# LoraWAN_Soil_Moisture_Sensor_v2_0.net
KiCad netlist of a schematic drawn in EAGLE
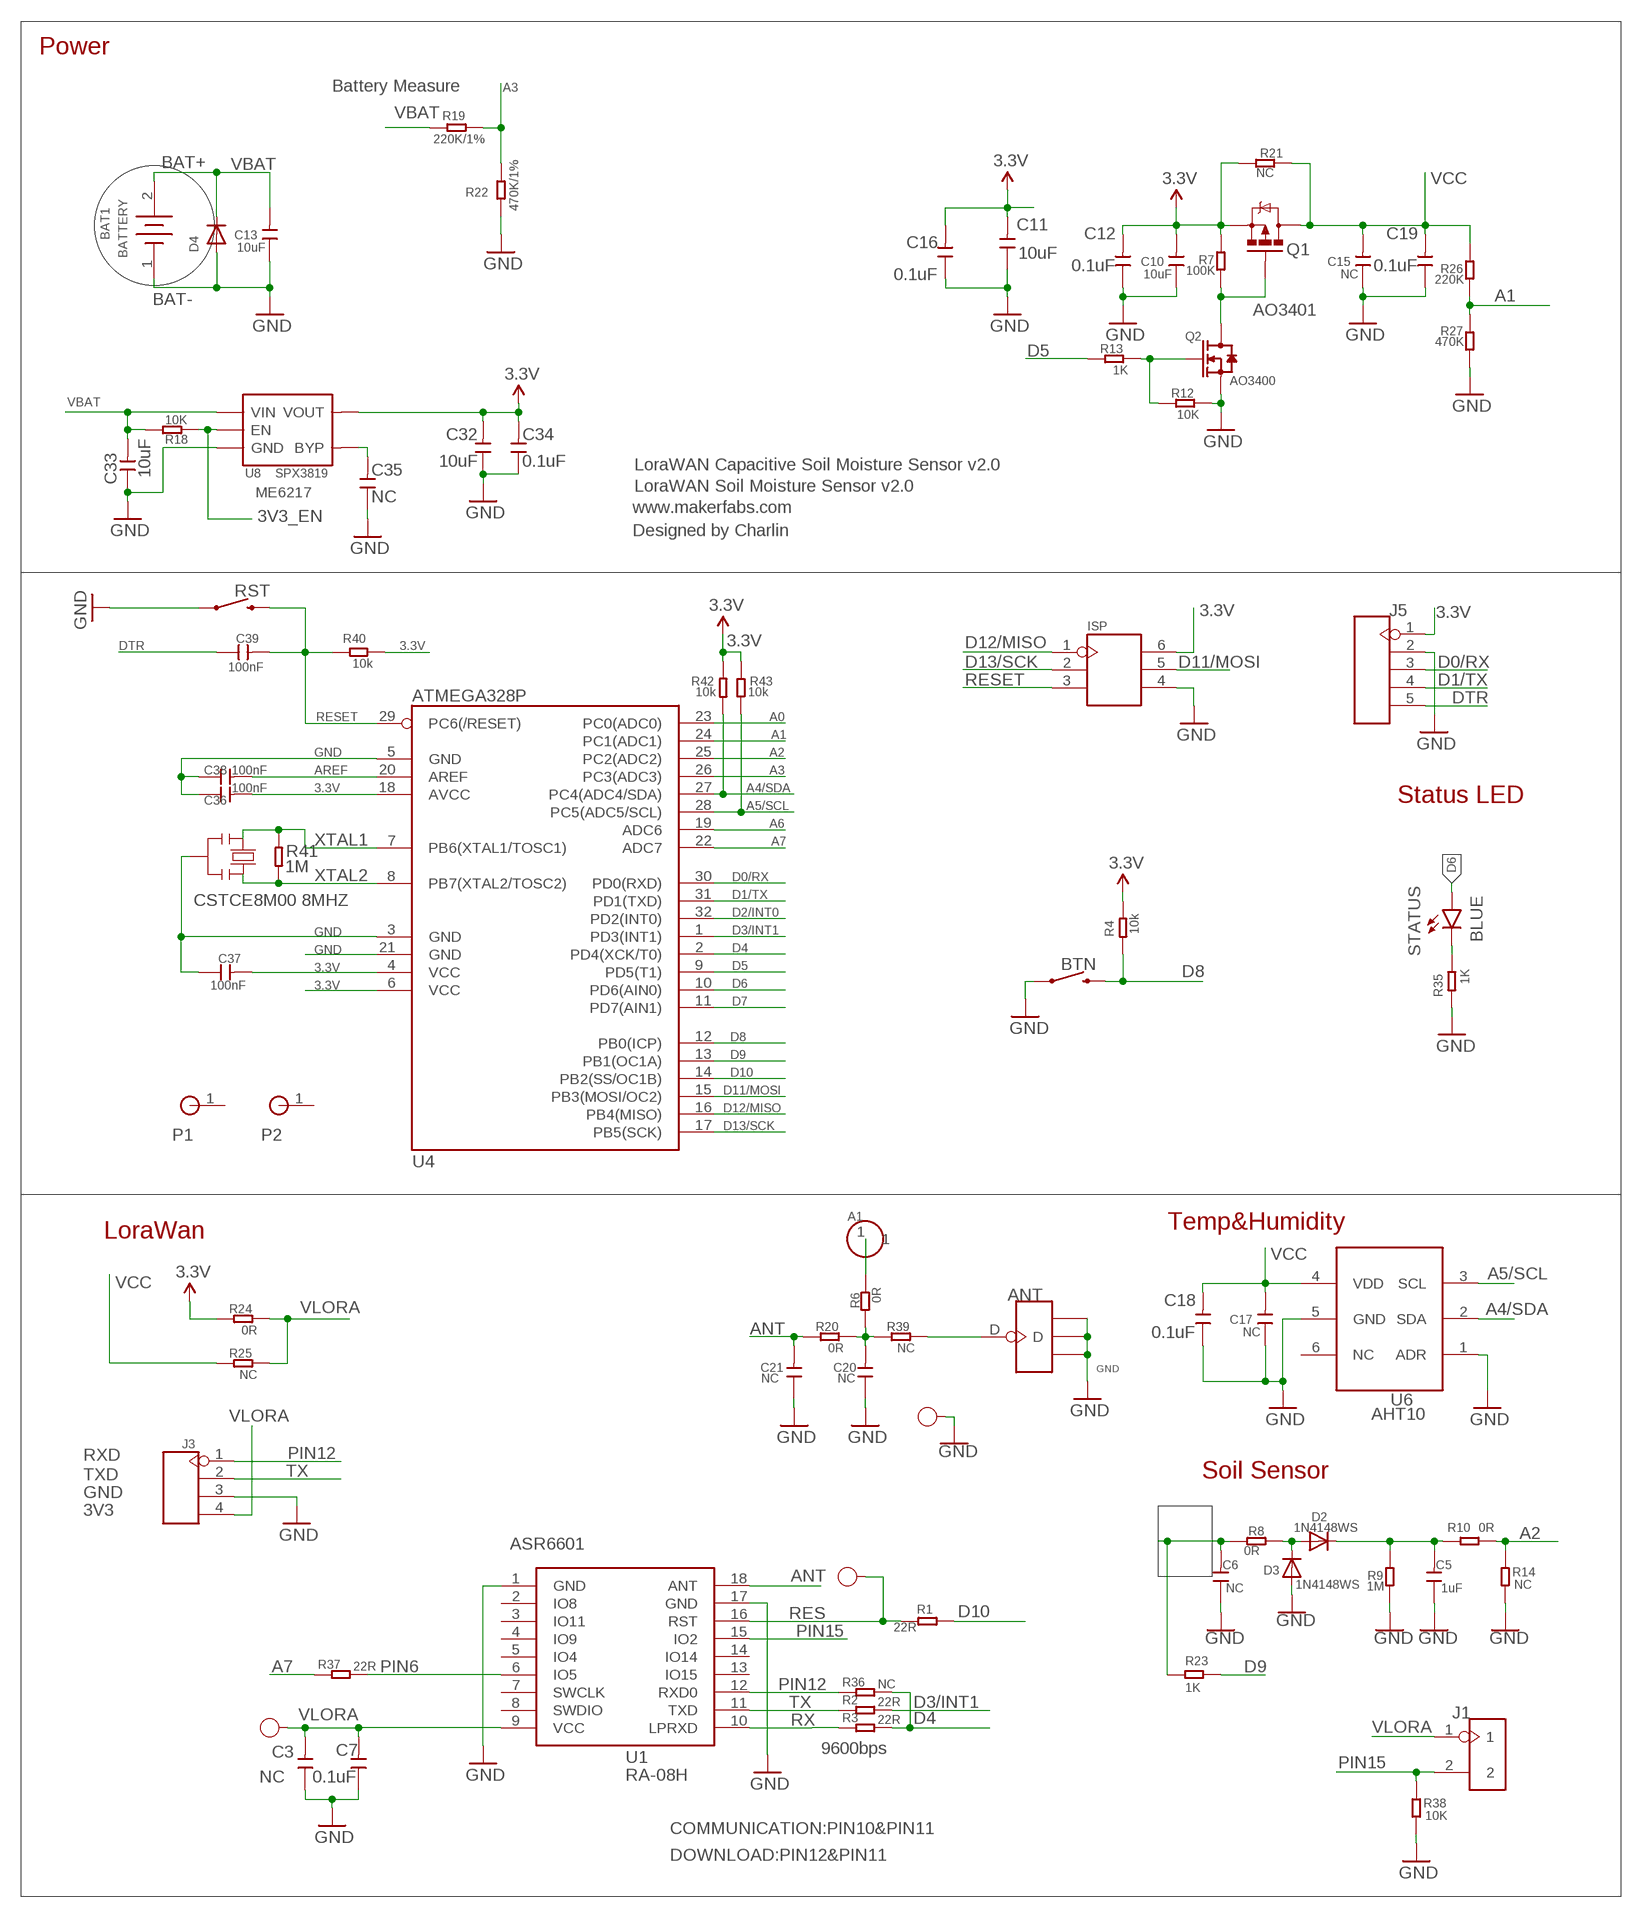
[diagram p0: schematic, sheet 1]

(export (version "E")
  (design (tool "Eeschema 10.0.6"))
  (components
    (comp (ref "3V3")
      (value "TEST-POINT'4545'")
      (footprint "eagle-import:TP-D45MIL")
      (fields (field (name "PARTNO") "DNP") (field (name "PARTNO_1") "DNP"))
      (libsource (lib "eagle-import") (part "TEST-POINT'4545'"))
    )
    (comp (ref "A1")
      (value "HEADER-1P-50")
      (footprint "eagle-import:1P-100_50MIL")
      (libsource (lib "eagle-import") (part "HEADER-1P-50"))
    )
    (comp (ref "ANT")
      (value "ANTENNA-U-FL")
      (footprint "eagle-import:4P-U-FL")
      (libsource (lib "eagle-import") (part "ANTENNA-U-FL"))
    )
    (comp (ref "BAT1")
      (value "BATTERY")
      (footprint "eagle-import:BATTERY")
      (libsource (lib "eagle-import") (part "BATTERY"))
    )
    (comp (ref "BTN")
      (value "MOMENTARY-SWITCH-SPST-SMD-6.0X3.5MM")
      (footprint "eagle-import:TACTILE_SWITCH_SMD_6.0X3.5MM")
      (fields (field (name "PROD_ID") "SWCH-00815") (field (name "SF_SKU") "COM-08229"))
      (libsource (lib "eagle-import") (part "MOMENTARY-SWITCH-SPST-SMD-6.0X3.5MM"))
    )
    (comp (ref "C3")
      (value "NC")
      (footprint "eagle-import:0603")
      (libsource (lib "eagle-import") (part "C-0603"))
    )
    (comp (ref "C5")
      (value "1uF")
      (footprint "eagle-import:DISCRETE_C0603")
      (libsource (lib "eagle-import") (part "DISCRETE_C-0603"))
    )
    (comp (ref "C6")
      (value "NC")
      (footprint "eagle-import:DISCRETE_C0603")
      (libsource (lib "eagle-import") (part "DISCRETE_C-0603"))
    )
    (comp (ref "C7")
      (value "0.1uF")
      (footprint "eagle-import:0603")
      (libsource (lib "eagle-import") (part "C-0603"))
    )
    (comp (ref "C10")
      (value "10uF")
      (footprint "eagle-import:0603")
      (libsource (lib "eagle-import") (part "C-0603"))
    )
    (comp (ref "C11")
      (value "10uF")
      (footprint "eagle-import:0603")
      (libsource (lib "eagle-import") (part "C-0603"))
    )
    (comp (ref "C12")
      (value "0.1uF")
      (footprint "eagle-import:0603")
      (libsource (lib "eagle-import") (part "C-0603"))
    )
    (comp (ref "C13")
      (value "10uF")
      (footprint "eagle-import:0603")
      (libsource (lib "eagle-import") (part "C-0603"))
    )
    (comp (ref "C15")
      (value "NC")
      (footprint "eagle-import:0603")
      (libsource (lib "eagle-import") (part "C-0603"))
    )
    (comp (ref "C16")
      (value "0.1uF")
      (footprint "eagle-import:0603")
      (libsource (lib "eagle-import") (part "C-0603"))
    )
    (comp (ref "C17")
      (value "NC")
      (footprint "eagle-import:0603")
      (libsource (lib "eagle-import") (part "C-0603"))
    )
    (comp (ref "C18")
      (value "0.1uF")
      (footprint "eagle-import:0603")
      (libsource (lib "eagle-import") (part "C-0603"))
    )
    (comp (ref "C19")
      (value "0.1uF")
      (footprint "eagle-import:0603")
      (libsource (lib "eagle-import") (part "C-0603"))
    )
    (comp (ref "C20")
      (value "NC")
      (footprint "eagle-import:0603")
      (libsource (lib "eagle-import") (part "C-0603"))
    )
    (comp (ref "C21")
      (value "NC")
      (footprint "eagle-import:0603")
      (libsource (lib "eagle-import") (part "C-0603"))
    )
    (comp (ref "C32")
      (value "10uF")
      (footprint "eagle-import:0603")
      (libsource (lib "eagle-import") (part "C-0603"))
    )
    (comp (ref "C33")
      (value "10uF")
      (footprint "eagle-import:0603")
      (libsource (lib "eagle-import") (part "C-0603"))
    )
    (comp (ref "C34")
      (value "0.1uF")
      (footprint "eagle-import:0603")
      (libsource (lib "eagle-import") (part "C-0603"))
    )
    (comp (ref "C35")
      (value "NC")
      (footprint "eagle-import:0603")
      (libsource (lib "eagle-import") (part "C-0603"))
    )
    (comp (ref "C36")
      (value "100nF")
      (footprint "eagle-import:0603")
      (libsource (lib "eagle-import") (part "C-0603"))
    )
    (comp (ref "C37")
      (value "100nF")
      (footprint "eagle-import:0603")
      (libsource (lib "eagle-import") (part "C-0603"))
    )
    (comp (ref "C38")
      (value "100nF")
      (footprint "eagle-import:0603")
      (libsource (lib "eagle-import") (part "C-0603"))
    )
    (comp (ref "C39")
      (value "100nF")
      (footprint "eagle-import:0603")
      (libsource (lib "eagle-import") (part "C-0603"))
    )
    (comp (ref "D2")
      (value "1N4148WS")
      (footprint "eagle-import:SOD-323F")
      (libsource (lib "eagle-import") (part "DIODESOD-323F"))
    )
    (comp (ref "D3")
      (value "1N4148WS")
      (footprint "eagle-import:SOD-323F")
      (libsource (lib "eagle-import") (part "DIODESOD-323F"))
    )
    (comp (ref "D4")
      (value "DIODESOD-323F")
      (footprint "eagle-import:SOD-323F")
      (libsource (lib "eagle-import") (part "DIODESOD-323F"))
    )
    (comp (ref "GND")
      (value "TEST-POINT'4545'")
      (footprint "eagle-import:TP-D45MIL")
      (fields (field (name "PARTNO") "DNP"))
      (libsource (lib "eagle-import") (part "TEST-POINT'4545'"))
    )
    (comp (ref "ISP")
      (value "HEADER-2X3P-SMD")
      (footprint "eagle-import:2X3P-2.54-SMD")
      (libsource (lib "eagle-import") (part "HEADER-2X3P-SMD"))
    )
    (comp (ref "J1")
      (value "HEADER-2P-2.0")
      (footprint "eagle-import:2P-2.0")
      (libsource (lib "eagle-import") (part "HEADER-2P-2.0"))
    )
    (comp (ref "J3")
      (value "HEADER-4P-60/35MILROUND")
      (footprint "eagle-import:4P-65_35ROUND")
      (libsource (lib "eagle-import") (part "HEADER-4P-60/35MILROUND"))
    )
    (comp (ref "J5")
      (value "HEADER-5P-2.54")
      (footprint "eagle-import:5P-2.54")
      (libsource (lib "eagle-import") (part "HEADER-5P-2.54"))
    )
    (comp (ref "P1")
      (value "HOLE-P1-2.2")
      (footprint "eagle-import:MTGNP1-220-1MM")
      (libsource (lib "eagle-import") (part "HOLE-P1-2.2"))
    )
    (comp (ref "P2")
      (value "HOLE-P1-2.2")
      (footprint "eagle-import:MTGNP1-220-1MM")
      (libsource (lib "eagle-import") (part "HOLE-P1-2.2"))
    )
    (comp (ref "Q1")
      (value "MOSFET-PCHANNEL")
      (footprint "eagle-import:SOT23-3")
      (libsource (lib "eagle-import") (part "MOSFET-PCHANNEL"))
    )
    (comp (ref "Q2")
      (value "AO3400")
      (footprint "eagle-import:DISCRETE_SOT23")
      (libsource (lib "eagle-import") (part "DISCRETE_MOSFET-NSOT23"))
    )
    (comp (ref "R1")
      (value "22R")
      (footprint "eagle-import:R0603")
      (libsource (lib "eagle-import") (part "R-0603"))
    )
    (comp (ref "R2")
      (value "22R")
      (footprint "eagle-import:R0603")
      (libsource (lib "eagle-import") (part "R-0603"))
    )
    (comp (ref "R3")
      (value "22R")
      (footprint "eagle-import:R0603")
      (libsource (lib "eagle-import") (part "R-0603"))
    )
    (comp (ref "R4")
      (value "10k")
      (footprint "eagle-import:R0603")
      (libsource (lib "eagle-import") (part "R-0603"))
    )
    (comp (ref "R6")
      (value "0R")
      (footprint "eagle-import:R0603")
      (libsource (lib "eagle-import") (part "R-0603"))
    )
    (comp (ref "R7")
      (value "100K")
      (footprint "eagle-import:R0603")
      (libsource (lib "eagle-import") (part "R-0603"))
    )
    (comp (ref "R8")
      (value "0R")
      (footprint "eagle-import:R0603")
      (libsource (lib "eagle-import") (part "R-0603"))
    )
    (comp (ref "R9")
      (value "1M")
      (footprint "eagle-import:R0603")
      (libsource (lib "eagle-import") (part "R-0603"))
    )
    (comp (ref "R10")
      (value "0R")
      (footprint "eagle-import:R0603")
      (libsource (lib "eagle-import") (part "R-0603"))
    )
    (comp (ref "R12")
      (value "10K")
      (footprint "eagle-import:R0603")
      (libsource (lib "eagle-import") (part "R-0603"))
    )
    (comp (ref "R13")
      (value "1K")
      (footprint "eagle-import:R0603")
      (libsource (lib "eagle-import") (part "R-0603"))
    )
    (comp (ref "R14")
      (value "NC")
      (footprint "eagle-import:R0603")
      (libsource (lib "eagle-import") (part "R-0603"))
    )
    (comp (ref "R18")
      (value "10K")
      (footprint "eagle-import:R0603")
      (libsource (lib "eagle-import") (part "R-0603"))
    )
    (comp (ref "R19")
      (value "220K/1%")
      (footprint "eagle-import:R0603")
      (libsource (lib "eagle-import") (part "R-0603"))
    )
    (comp (ref "R20")
      (value "0R")
      (footprint "eagle-import:R0603")
      (libsource (lib "eagle-import") (part "R-0603"))
    )
    (comp (ref "R21")
      (value "NC")
      (footprint "eagle-import:R0603")
      (libsource (lib "eagle-import") (part "R-0603"))
    )
    (comp (ref "R22")
      (value "470K/1%")
      (footprint "eagle-import:R0603")
      (libsource (lib "eagle-import") (part "R-0603"))
    )
    (comp (ref "R23")
      (value "1K")
      (footprint "eagle-import:R0603")
      (libsource (lib "eagle-import") (part "RES-0603"))
    )
    (comp (ref "R24")
      (value "0R")
      (footprint "eagle-import:R0603")
      (libsource (lib "eagle-import") (part "R-0603"))
    )
    (comp (ref "R25")
      (value "NC")
      (footprint "eagle-import:R0603")
      (libsource (lib "eagle-import") (part "R-0603"))
    )
    (comp (ref "R26")
      (value "220K")
      (footprint "eagle-import:R0603")
      (libsource (lib "eagle-import") (part "R-0603"))
    )
    (comp (ref "R27")
      (value "470K")
      (footprint "eagle-import:R0603")
      (libsource (lib "eagle-import") (part "R-0603"))
    )
    (comp (ref "R35")
      (value "1K")
      (footprint "eagle-import:R0603")
      (libsource (lib "eagle-import") (part "R-0603"))
    )
    (comp (ref "R36")
      (value "NC")
      (footprint "eagle-import:R0603")
      (libsource (lib "eagle-import") (part "R-0603"))
    )
    (comp (ref "R37")
      (value "22R")
      (footprint "eagle-import:R0603")
      (libsource (lib "eagle-import") (part "R-0603"))
    )
    (comp (ref "R38")
      (value "10K")
      (footprint "eagle-import:R0603")
      (libsource (lib "eagle-import") (part "R-0603"))
    )
    (comp (ref "R39")
      (value "NC")
      (footprint "eagle-import:R0603")
      (libsource (lib "eagle-import") (part "R-0603"))
    )
    (comp (ref "R40")
      (value "10k")
      (footprint "eagle-import:R0603")
      (libsource (lib "eagle-import") (part "R-0603"))
    )
    (comp (ref "R41")
      (value "1M")
      (footprint "eagle-import:R0603")
      (libsource (lib "eagle-import") (part "R-0603"))
    )
    (comp (ref "R42")
      (value "10k")
      (footprint "eagle-import:R0603")
      (libsource (lib "eagle-import") (part "R-0603"))
    )
    (comp (ref "R43")
      (value "10k")
      (footprint "eagle-import:R0603")
      (libsource (lib "eagle-import") (part "R-0603"))
    )
    (comp (ref "RES")
      (value "TEST-POINT'4545'")
      (footprint "eagle-import:TP-D45MIL")
      (fields (field (name "PARTNO") "DNP") (field (name "PARTNO_1") "DNP"))
      (libsource (lib "eagle-import") (part "TEST-POINT'4545'"))
    )
    (comp (ref "RST")
      (value "MOMENTARY-SWITCH-SPST-SMD-6.0X3.5MM")
      (footprint "eagle-import:TACTILE_SWITCH_SMD_6.0X3.5MM")
      (libsource (lib "eagle-import") (part "MOMENTARY-SWITCH-SPST-SMD-6.0X3.5MM"))
    )
    (comp (ref "STATUS")
      (value "BLUE")
      (footprint "eagle-import:LED-0603")
      (libsource (lib "eagle-import") (part "LED-BLUE0603"))
    )
    (comp (ref "U1")
      (value "RA-08H")
      (footprint "eagle-import:RA-08H")
      (libsource (lib "eagle-import") (part "RA-08H"))
    )
    (comp (ref "U4")
      (value "ATMEGA328P")
      (footprint "eagle-import:TQFP32")
      (libsource (lib "eagle-import") (part "ATMEGA8/168/328"))
    )
    (comp (ref "U6")
      (value "AHT10")
      (footprint "eagle-import:SMD6-127P-400L500W")
      (libsource (lib "eagle-import") (part "AHT10"))
    )
    (comp (ref "U8")
      (value "SPX3819")
      (footprint "eagle-import:SOT23-5")
      (libsource (lib "eagle-import") (part "SPX3819"))
    )
    (comp (ref "Y1")
      (value "CSTCE8M00 8MHZ")
      (footprint "eagle-import:RESONATOR")
      (libsource (lib "eagle-import") (part "RESONATORMU"))
    )
  )
  (nets
    (net (code "1") (name "/3V3_EN") (class "Default")
      (node (ref "R18") (pin "2") (pinfunction "2_2") (pintype "passive"))
      (node (ref "U8") (pin "3") (pinfunction "EN_3") (pintype "bidirectional"))
    )
    (net (code "2") (name "/A0") (class "Default")
      (node (ref "U4") (pin "23") (pinfunction "PC0(ADC0)_23") (pintype "bidirectional"))
    )
    (net (code "3") (name "/A1") (class "Default")
      (node (ref "R26") (pin "1") (pinfunction "1_1") (pintype "passive"))
      (node (ref "R27") (pin "2") (pinfunction "2_2") (pintype "passive"))
      (node (ref "U4") (pin "24") (pinfunction "PC1(ADC1)_24") (pintype "bidirectional"))
    )
    (net (code "4") (name "/A2") (class "Default")
      (node (ref "R10") (pin "2") (pinfunction "2_2") (pintype "passive"))
      (node (ref "R14") (pin "1") (pinfunction "1_1") (pintype "passive"))
      (node (ref "U4") (pin "25") (pinfunction "PC2(ADC2)_25") (pintype "bidirectional"))
    )
    (net (code "5") (name "/A3") (class "Default")
      (node (ref "R19") (pin "1") (pinfunction "1_1") (pintype "passive"))
      (node (ref "R22") (pin "2") (pinfunction "2_2") (pintype "passive"))
      (node (ref "U4") (pin "26") (pinfunction "PC3(ADC3)_26") (pintype "bidirectional"))
    )
    (net (code "6") (name "/A4{slash}SDA") (class "Default")
      (node (ref "R42") (pin "2") (pinfunction "2_2") (pintype "passive"))
      (node (ref "U4") (pin "27") (pinfunction "PC4(ADC4/SDA)_27") (pintype "bidirectional"))
      (node (ref "U6") (pin "2") (pinfunction "SDA_2") (pintype "bidirectional"))
    )
    (net (code "7") (name "/A5{slash}SCL") (class "Default")
      (node (ref "R43") (pin "2") (pinfunction "2_2") (pintype "passive"))
      (node (ref "U4") (pin "28") (pinfunction "PC5(ADC5/SCL)_28") (pintype "bidirectional"))
      (node (ref "U6") (pin "3") (pinfunction "SCL_3") (pintype "bidirectional"))
    )
    (net (code "8") (name "/A6") (class "Default")
      (node (ref "U4") (pin "19") (pinfunction "ADC6_19") (pintype "bidirectional"))
    )
    (net (code "9") (name "/A7") (class "Default")
      (node (ref "R37") (pin "1") (pinfunction "1_1") (pintype "passive"))
      (node (ref "U4") (pin "22") (pinfunction "ADC7_22") (pintype "bidirectional"))
    )
    (net (code "10") (name "/ANT") (class "Default")
      (node (ref "C21") (pin "2") (pinfunction "2_2") (pintype "passive"))
      (node (ref "R20") (pin "2") (pinfunction "2_2") (pintype "passive"))
      (node (ref "U1") (pin "18") (pinfunction "ANT_18") (pintype "bidirectional"))
    )
    (net (code "11") (name "/AREF") (class "Default")
      (node (ref "C38") (pin "2") (pinfunction "2_2") (pintype "passive"))
      (node (ref "U4") (pin "20") (pinfunction "AREF_20") (pintype "bidirectional"))
    )
    (net (code "12") (name "/D0{slash}RX") (class "Default")
      (node (ref "J5") (pin "3") (pinfunction "3_3") (pintype "bidirectional"))
      (node (ref "U4") (pin "30") (pinfunction "PD0(RXD)_30") (pintype "bidirectional"))
    )
    (net (code "13") (name "/D1{slash}TX") (class "Default")
      (node (ref "J5") (pin "4") (pinfunction "4_4") (pintype "bidirectional"))
      (node (ref "U4") (pin "31") (pinfunction "PD1(TXD)_31") (pintype "bidirectional"))
    )
    (net (code "14") (name "/D2{slash}INT0") (class "Default")
      (node (ref "U4") (pin "32") (pinfunction "PD2(INT0)_32") (pintype "bidirectional"))
    )
    (net (code "15") (name "/D3{slash}INT1") (class "Default")
      (node (ref "R2") (pin "2") (pinfunction "2_2") (pintype "passive"))
      (node (ref "U4") (pin "1") (pinfunction "PD3(INT1)_1") (pintype "bidirectional"))
    )
    (net (code "16") (name "/D4") (class "Default")
      (node (ref "R3") (pin "2") (pinfunction "2_2") (pintype "passive"))
      (node (ref "R36") (pin "2") (pinfunction "2_2") (pintype "passive"))
      (node (ref "U4") (pin "2") (pinfunction "PD4(XCK/T0)_2") (pintype "bidirectional"))
    )
    (net (code "17") (name "/D5") (class "Default")
      (node (ref "R13") (pin "2") (pinfunction "2_2") (pintype "passive"))
      (node (ref "U4") (pin "9") (pinfunction "PD5(T1)_9") (pintype "bidirectional"))
    )
    (net (code "18") (name "/D7") (class "Default")
      (node (ref "U4") (pin "11") (pinfunction "PD7(AIN1)_11") (pintype "bidirectional"))
    )
    (net (code "19") (name "/D8") (class "Default")
      (node (ref "BTN") (pin "2") (pinfunction "2_2") (pintype "passive"))
      (node (ref "R4") (pin "2") (pinfunction "2_2") (pintype "passive"))
      (node (ref "U4") (pin "12") (pinfunction "PB0(ICP)_12") (pintype "bidirectional"))
    )
    (net (code "20") (name "/D9") (class "Default")
      (node (ref "R23") (pin "2") (pinfunction "2_2") (pintype "passive"))
      (node (ref "U4") (pin "13") (pinfunction "PB1(OC1A)_13") (pintype "bidirectional"))
    )
    (net (code "21") (name "/D10") (class "Default")
      (node (ref "R1") (pin "2") (pinfunction "2_2") (pintype "passive"))
      (node (ref "U4") (pin "14") (pinfunction "PB2(SS/OC1B)_14") (pintype "bidirectional"))
    )
    (net (code "22") (name "/D11{slash}MOSI") (class "Default")
      (node (ref "ISP") (pin "5") (pinfunction "5_5") (pintype "bidirectional"))
      (node (ref "U4") (pin "15") (pinfunction "PB3(MOSI/OC2)_15") (pintype "bidirectional"))
    )
    (net (code "23") (name "/D12{slash}MISO") (class "Default")
      (node (ref "ISP") (pin "1") (pinfunction "1_1") (pintype "bidirectional"))
      (node (ref "U4") (pin "16") (pinfunction "PB4(MISO)_16") (pintype "bidirectional"))
    )
    (net (code "24") (name "/D13{slash}SCK") (class "Default")
      (node (ref "ISP") (pin "2") (pinfunction "2_2") (pintype "bidirectional"))
      (node (ref "U4") (pin "17") (pinfunction "PB5(SCK)_17") (pintype "bidirectional"))
    )
    (net (code "25") (name "/DTR") (class "Default")
      (node (ref "C39") (pin "1") (pinfunction "1_1") (pintype "passive"))
      (node (ref "J5") (pin "5") (pinfunction "5_5") (pintype "bidirectional"))
    )
    (net (code "26") (name "/PIN6") (class "Default")
      (node (ref "R37") (pin "2") (pinfunction "2_2") (pintype "passive"))
      (node (ref "U1") (pin "6") (pinfunction "IO5_6") (pintype "bidirectional"))
    )
    (net (code "27") (name "/PIN12") (class "Default")
      (node (ref "J3") (pin "1") (pinfunction "P$1_1") (pintype "bidirectional"))
      (node (ref "R36") (pin "1") (pinfunction "1_1") (pintype "passive"))
      (node (ref "U1") (pin "12") (pinfunction "RXD0_12") (pintype "bidirectional"))
    )
    (net (code "28") (name "/PIN15") (class "Default")
      (node (ref "J1") (pin "2") (pinfunction "2_2") (pintype "bidirectional"))
      (node (ref "R38") (pin "1") (pinfunction "1_1") (pintype "passive"))
      (node (ref "U1") (pin "15") (pinfunction "IO2_15") (pintype "bidirectional"))
    )
    (net (code "29") (name "/RES") (class "Default")
      (node (ref "R1") (pin "1") (pinfunction "1_1") (pintype "passive"))
      (node (ref "RES") (pin "T") (pinfunction "T_T") (pintype "bidirectional"))
      (node (ref "U1") (pin "16") (pinfunction "RST_16") (pintype "bidirectional"))
    )
    (net (code "30") (name "/RESET") (class "Default")
      (node (ref "C39") (pin "2") (pinfunction "2_2") (pintype "passive"))
      (node (ref "ISP") (pin "3") (pinfunction "3_3") (pintype "bidirectional"))
      (node (ref "R40") (pin "2") (pinfunction "2_2") (pintype "passive"))
      (node (ref "RST") (pin "2") (pinfunction "2_2") (pintype "passive"))
      (node (ref "U4") (pin "29") (pinfunction "PC6(/RESET)_29") (pintype "bidirectional"))
    )
    (net (code "31") (name "/RX") (class "Default")
      (node (ref "R3") (pin "1") (pinfunction "1_1") (pintype "passive"))
      (node (ref "U1") (pin "10") (pinfunction "LPRXD_10") (pintype "bidirectional"))
    )
    (net (code "32") (name "/TX") (class "Default")
      (node (ref "J3") (pin "2") (pinfunction "P$2_2") (pintype "bidirectional"))
      (node (ref "R2") (pin "1") (pinfunction "1_1") (pintype "passive"))
      (node (ref "U1") (pin "11") (pinfunction "TXD_11") (pintype "bidirectional"))
    )
    (net (code "33") (name "/VBAT") (class "Default")
      (node (ref "BAT1") (pin "2") (pinfunction "2_2") (pintype "bidirectional"))
      (node (ref "C13") (pin "2") (pinfunction "2_2") (pintype "passive"))
      (node (ref "C33") (pin "2") (pinfunction "2_2") (pintype "passive"))
      (node (ref "D4") (pin "C") (pinfunction "C_C") (pintype "passive"))
      (node (ref "R18") (pin "1") (pinfunction "1_1") (pintype "passive"))
      (node (ref "R19") (pin "2") (pinfunction "2_2") (pintype "passive"))
      (node (ref "U8") (pin "1") (pinfunction "VIN_1") (pintype "bidirectional"))
    )
    (net (code "34") (name "/VCC") (class "Default")
      (node (ref "C15") (pin "2") (pinfunction "2_2") (pintype "passive"))
      (node (ref "C17") (pin "2") (pinfunction "2_2") (pintype "passive"))
      (node (ref "C18") (pin "2") (pinfunction "2_2") (pintype "passive"))
      (node (ref "C19") (pin "2") (pinfunction "2_2") (pintype "passive"))
      (node (ref "Q1") (pin "3") (pinfunction "D_3") (pintype "passive"))
      (node (ref "R21") (pin "1") (pinfunction "1_1") (pintype "passive"))
      (node (ref "R25") (pin "2") (pinfunction "2_2") (pintype "passive"))
      (node (ref "R26") (pin "2") (pinfunction "2_2") (pintype "passive"))
      (node (ref "U6") (pin "4") (pinfunction "VDD_4") (pintype "bidirectional"))
    )
    (net (code "35") (name "/VLORA") (class "Default")
      (node (ref "3V3") (pin "T") (pinfunction "T_T") (pintype "bidirectional"))
      (node (ref "C3") (pin "2") (pinfunction "2_2") (pintype "passive"))
      (node (ref "C7") (pin "2") (pinfunction "2_2") (pintype "passive"))
      (node (ref "J1") (pin "1") (pinfunction "1_1") (pintype "bidirectional"))
      (node (ref "J3") (pin "4") (pinfunction "P$4_4") (pintype "bidirectional"))
      (node (ref "R24") (pin "1") (pinfunction "1_1") (pintype "passive"))
      (node (ref "R25") (pin "1") (pinfunction "1_1") (pintype "passive"))
      (node (ref "U1") (pin "9") (pinfunction "VCC_9") (pintype "bidirectional"))
    )
    (net (code "36") (name "/XTAL1") (class "Default")
      (node (ref "R41") (pin "2") (pinfunction "2_2") (pintype "passive"))
      (node (ref "U4") (pin "7") (pinfunction "PB6(XTAL1/TOSC1)_7") (pintype "bidirectional"))
      (node (ref "Y1") (pin "1") (pinfunction "1_1") (pintype "passive"))
    )
    (net (code "37") (name "/XTAL2") (class "Default")
      (node (ref "R41") (pin "1") (pinfunction "1_1") (pintype "passive"))
      (node (ref "U4") (pin "8") (pinfunction "PB7(XTAL2/TOSC2)_8") (pintype "bidirectional"))
      (node (ref "Y1") (pin "3") (pinfunction "3_3") (pintype "passive"))
    )
    (net (code "38") (name "3.3V") (class "Default")
      (node (ref "C10") (pin "2") (pinfunction "2_2") (pintype "passive"))
      (node (ref "C11") (pin "2") (pinfunction "2_2") (pintype "passive"))
      (node (ref "C12") (pin "2") (pinfunction "2_2") (pintype "passive"))
      (node (ref "C16") (pin "2") (pinfunction "2_2") (pintype "passive"))
      (node (ref "C32") (pin "2") (pinfunction "2_2") (pintype "passive"))
      (node (ref "C34") (pin "2") (pinfunction "2_2") (pintype "passive"))
      (node (ref "C36") (pin "2") (pinfunction "2_2") (pintype "passive"))
      (node (ref "C37") (pin "2") (pinfunction "2_2") (pintype "passive"))
      (node (ref "ISP") (pin "6") (pinfunction "6_6") (pintype "bidirectional"))
      (node (ref "J5") (pin "1") (pinfunction "1_1") (pintype "bidirectional"))
      (node (ref "Q1") (pin "2") (pinfunction "S_2") (pintype "passive"))
      (node (ref "R21") (pin "2") (pinfunction "2_2") (pintype "passive"))
      (node (ref "R24") (pin "2") (pinfunction "2_2") (pintype "passive"))
      (node (ref "R4") (pin "1") (pinfunction "1_1") (pintype "passive"))
      (node (ref "R40") (pin "1") (pinfunction "1_1") (pintype "passive"))
      (node (ref "R42") (pin "1") (pinfunction "1_1") (pintype "passive"))
      (node (ref "R43") (pin "1") (pinfunction "1_1") (pintype "passive"))
      (node (ref "R7") (pin "2") (pinfunction "2_2") (pintype "passive"))
      (node (ref "U4") (pin "18") (pinfunction "AVCC_18") (pintype "bidirectional"))
      (node (ref "U4") (pin "4") (pinfunction "VCC_4") (pintype "bidirectional"))
      (node (ref "U4") (pin "6") (pinfunction "VCC_6") (pintype "bidirectional"))
      (node (ref "U8") (pin "5") (pinfunction "VOUT_5") (pintype "bidirectional"))
    )
    (net (code "39") (name "D6") (class "Default")
      (node (ref "STATUS") (pin "A") (pinfunction "A_A") (pintype "passive"))
      (node (ref "U4") (pin "10") (pinfunction "PD6(AIN0)_10") (pintype "bidirectional"))
    )
    (net (code "40") (name "GND") (class "Default")
      (node (ref "ANT") (pin "GND1") (pinfunction "GND1_GND1") (pintype "bidirectional"))
      (node (ref "ANT") (pin "GND2") (pinfunction "GND2_GND2") (pintype "bidirectional"))
      (node (ref "ANT") (pin "GND3") (pinfunction "GND3_GND3") (pintype "bidirectional"))
      (node (ref "BAT1") (pin "1") (pinfunction "1_1") (pintype "bidirectional"))
      (node (ref "BTN") (pin "1") (pinfunction "1_1") (pintype "passive"))
      (node (ref "C10") (pin "1") (pinfunction "1_1") (pintype "passive"))
      (node (ref "C11") (pin "1") (pinfunction "1_1") (pintype "passive"))
      (node (ref "C12") (pin "1") (pinfunction "1_1") (pintype "passive"))
      (node (ref "C13") (pin "1") (pinfunction "1_1") (pintype "passive"))
      (node (ref "C15") (pin "1") (pinfunction "1_1") (pintype "passive"))
      (node (ref "C16") (pin "1") (pinfunction "1_1") (pintype "passive"))
      (node (ref "C17") (pin "1") (pinfunction "1_1") (pintype "passive"))
      (node (ref "C18") (pin "1") (pinfunction "1_1") (pintype "passive"))
      (node (ref "C19") (pin "1") (pinfunction "1_1") (pintype "passive"))
      (node (ref "C20") (pin "1") (pinfunction "1_1") (pintype "passive"))
      (node (ref "C21") (pin "1") (pinfunction "1_1") (pintype "passive"))
      (node (ref "C3") (pin "1") (pinfunction "1_1") (pintype "passive"))
      (node (ref "C32") (pin "1") (pinfunction "1_1") (pintype "passive"))
      (node (ref "C33") (pin "1") (pinfunction "1_1") (pintype "passive"))
      (node (ref "C34") (pin "1") (pinfunction "1_1") (pintype "passive"))
      (node (ref "C35") (pin "1") (pinfunction "1_1") (pintype "passive"))
      (node (ref "C36") (pin "1") (pinfunction "1_1") (pintype "passive"))
      (node (ref "C37") (pin "1") (pinfunction "1_1") (pintype "passive"))
      (node (ref "C38") (pin "1") (pinfunction "1_1") (pintype "passive"))
      (node (ref "C5") (pin "1") (pinfunction "1_1") (pintype "passive"))
      (node (ref "C6") (pin "1") (pinfunction "1_1") (pintype "passive"))
      (node (ref "C7") (pin "1") (pinfunction "1_1") (pintype "passive"))
      (node (ref "D3") (pin "A") (pinfunction "A_A") (pintype "passive"))
      (node (ref "D4") (pin "A") (pinfunction "A_A") (pintype "passive"))
      (node (ref "GND") (pin "T") (pinfunction "T_T") (pintype "bidirectional"))
      (node (ref "ISP") (pin "4") (pinfunction "4_4") (pintype "bidirectional"))
      (node (ref "J3") (pin "3") (pinfunction "P$3_3") (pintype "bidirectional"))
      (node (ref "J5") (pin "2") (pinfunction "2_2") (pintype "bidirectional"))
      (node (ref "Q2") (pin "2") (pinfunction "S_2") (pintype "passive"))
      (node (ref "R12") (pin "1") (pinfunction "1_1") (pintype "passive"))
      (node (ref "R14") (pin "2") (pinfunction "2_2") (pintype "passive"))
      (node (ref "R22") (pin "1") (pinfunction "1_1") (pintype "passive"))
      (node (ref "R27") (pin "1") (pinfunction "1_1") (pintype "passive"))
      (node (ref "R35") (pin "2") (pinfunction "2_2") (pintype "passive"))
      (node (ref "R38") (pin "2") (pinfunction "2_2") (pintype "passive"))
      (node (ref "R9") (pin "1") (pinfunction "1_1") (pintype "passive"))
      (node (ref "RST") (pin "1") (pinfunction "1_1") (pintype "passive"))
      (node (ref "U1") (pin "1") (pinfunction "GND_1") (pintype "bidirectional"))
      (node (ref "U1") (pin "17") (pinfunction "GND_17") (pintype "bidirectional"))
      (node (ref "U4") (pin "21") (pinfunction "GND_21") (pintype "bidirectional"))
      (node (ref "U4") (pin "3") (pinfunction "GND_3") (pintype "bidirectional"))
      (node (ref "U4") (pin "5") (pinfunction "GND_5") (pintype "bidirectional"))
      (node (ref "U6") (pin "1") (pinfunction "ADR_1") (pintype "bidirectional"))
      (node (ref "U6") (pin "5") (pinfunction "GND_5") (pintype "bidirectional"))
      (node (ref "U8") (pin "2") (pinfunction "GND_2") (pintype "bidirectional"))
      (node (ref "Y1") (pin "2") (pinfunction "2_2") (pintype "passive"))
    )
    (net (code "41") (name "Net-(A1-Pad1)") (class "Default")
      (node (ref "A1") (pin "1") (pinfunction "1_1") (pintype "bidirectional"))
      (node (ref "R6") (pin "1") (pinfunction "1_1") (pintype "passive"))
    )
    (net (code "42") (name "Net-(ANT-PadD)") (class "Default")
      (node (ref "ANT") (pin "D") (pinfunction "D_D") (pintype "bidirectional"))
      (node (ref "R39") (pin "1") (pinfunction "1_1") (pintype "passive"))
    )
    (net (code "43") (name "Net-(C5-Pad2)") (class "Default")
      (node (ref "C5") (pin "2") (pinfunction "2_2") (pintype "passive"))
      (node (ref "D2") (pin "C") (pinfunction "C_C") (pintype "passive"))
      (node (ref "R10") (pin "1") (pinfunction "1_1") (pintype "passive"))
      (node (ref "R9") (pin "2") (pinfunction "2_2") (pintype "passive"))
    )
    (net (code "44") (name "Net-(C6-Pad2)") (class "Default")
      (node (ref "C6") (pin "2") (pinfunction "2_2") (pintype "passive"))
      (node (ref "R23") (pin "1") (pinfunction "1_1") (pintype "passive"))
      (node (ref "R8") (pin "1") (pinfunction "1_1") (pintype "passive"))
    )
    (net (code "45") (name "Net-(C20-Pad2)") (class "Default")
      (node (ref "C20") (pin "2") (pinfunction "2_2") (pintype "passive"))
      (node (ref "R20") (pin "1") (pinfunction "1_1") (pintype "passive"))
      (node (ref "R39") (pin "2") (pinfunction "2_2") (pintype "passive"))
      (node (ref "R6") (pin "2") (pinfunction "2_2") (pintype "passive"))
    )
    (net (code "46") (name "Net-(D2-PadA)") (class "Default")
      (node (ref "D2") (pin "A") (pinfunction "A_A") (pintype "passive"))
      (node (ref "D3") (pin "C") (pinfunction "C_C") (pintype "passive"))
      (node (ref "R8") (pin "2") (pinfunction "2_2") (pintype "passive"))
    )
    (net (code "47") (name "Net-(Q1-G)") (class "Default")
      (node (ref "Q1") (pin "1") (pinfunction "G_1") (pintype "passive"))
      (node (ref "Q2") (pin "3") (pinfunction "D_3") (pintype "passive"))
      (node (ref "R7") (pin "1") (pinfunction "1_1") (pintype "passive"))
    )
    (net (code "48") (name "Net-(Q2-G)") (class "Default")
      (node (ref "Q2") (pin "1") (pinfunction "G_1") (pintype "passive"))
      (node (ref "R12") (pin "2") (pinfunction "2_2") (pintype "passive"))
      (node (ref "R13") (pin "1") (pinfunction "1_1") (pintype "passive"))
    )
    (net (code "49") (name "Net-(R35-Pad1)") (class "Default")
      (node (ref "R35") (pin "1") (pinfunction "1_1") (pintype "passive"))
      (node (ref "STATUS") (pin "C") (pinfunction "C_C") (pintype "passive"))
    )
    (net (code "50") (name "Net-(U8-BYP)") (class "Default")
      (node (ref "C35") (pin "2") (pinfunction "2_2") (pintype "passive"))
      (node (ref "U8") (pin "4") (pinfunction "BYP_4") (pintype "bidirectional"))
    )
    (net (code "51") (name "unconnected-(P1-P$1-Pad1)") (class "Default")
      (node (ref "P1") (pin "1") (pinfunction "P$1_1") (pintype "bidirectional"))
    )
    (net (code "52") (name "unconnected-(P2-P$1-Pad1)") (class "Default")
      (node (ref "P2") (pin "1") (pinfunction "P$1_1") (pintype "bidirectional"))
    )
    (net (code "53") (name "unconnected-(U1-IO4-Pad5)") (class "Default")
      (node (ref "U1") (pin "5") (pinfunction "IO4_5") (pintype "bidirectional"))
    )
    (net (code "54") (name "unconnected-(U1-IO8-Pad2)") (class "Default")
      (node (ref "U1") (pin "2") (pinfunction "IO8_2") (pintype "bidirectional"))
    )
    (net (code "55") (name "unconnected-(U1-IO9-Pad4)") (class "Default")
      (node (ref "U1") (pin "4") (pinfunction "IO9_4") (pintype "bidirectional"))
    )
    (net (code "56") (name "unconnected-(U1-IO11-Pad3)") (class "Default")
      (node (ref "U1") (pin "3") (pinfunction "IO11_3") (pintype "bidirectional"))
    )
    (net (code "57") (name "unconnected-(U1-IO14-Pad14)") (class "Default")
      (node (ref "U1") (pin "14") (pinfunction "IO14_14") (pintype "bidirectional"))
    )
    (net (code "58") (name "unconnected-(U1-IO15-Pad13)") (class "Default")
      (node (ref "U1") (pin "13") (pinfunction "IO15_13") (pintype "bidirectional"))
    )
    (net (code "59") (name "unconnected-(U1-SWCLK-Pad7)") (class "Default")
      (node (ref "U1") (pin "7") (pinfunction "SWCLK_7") (pintype "bidirectional"))
    )
    (net (code "60") (name "unconnected-(U1-SWDIO-Pad8)") (class "Default")
      (node (ref "U1") (pin "8") (pinfunction "SWDIO_8") (pintype "bidirectional"))
    )
    (net (code "61") (name "unconnected-(U6-NC-Pad6)") (class "Default")
      (node (ref "U6") (pin "6") (pinfunction "NC_6") (pintype "bidirectional"))
    )
  )
)
